# MCU.net
KiCad netlist of a schematic drawn in EAGLE
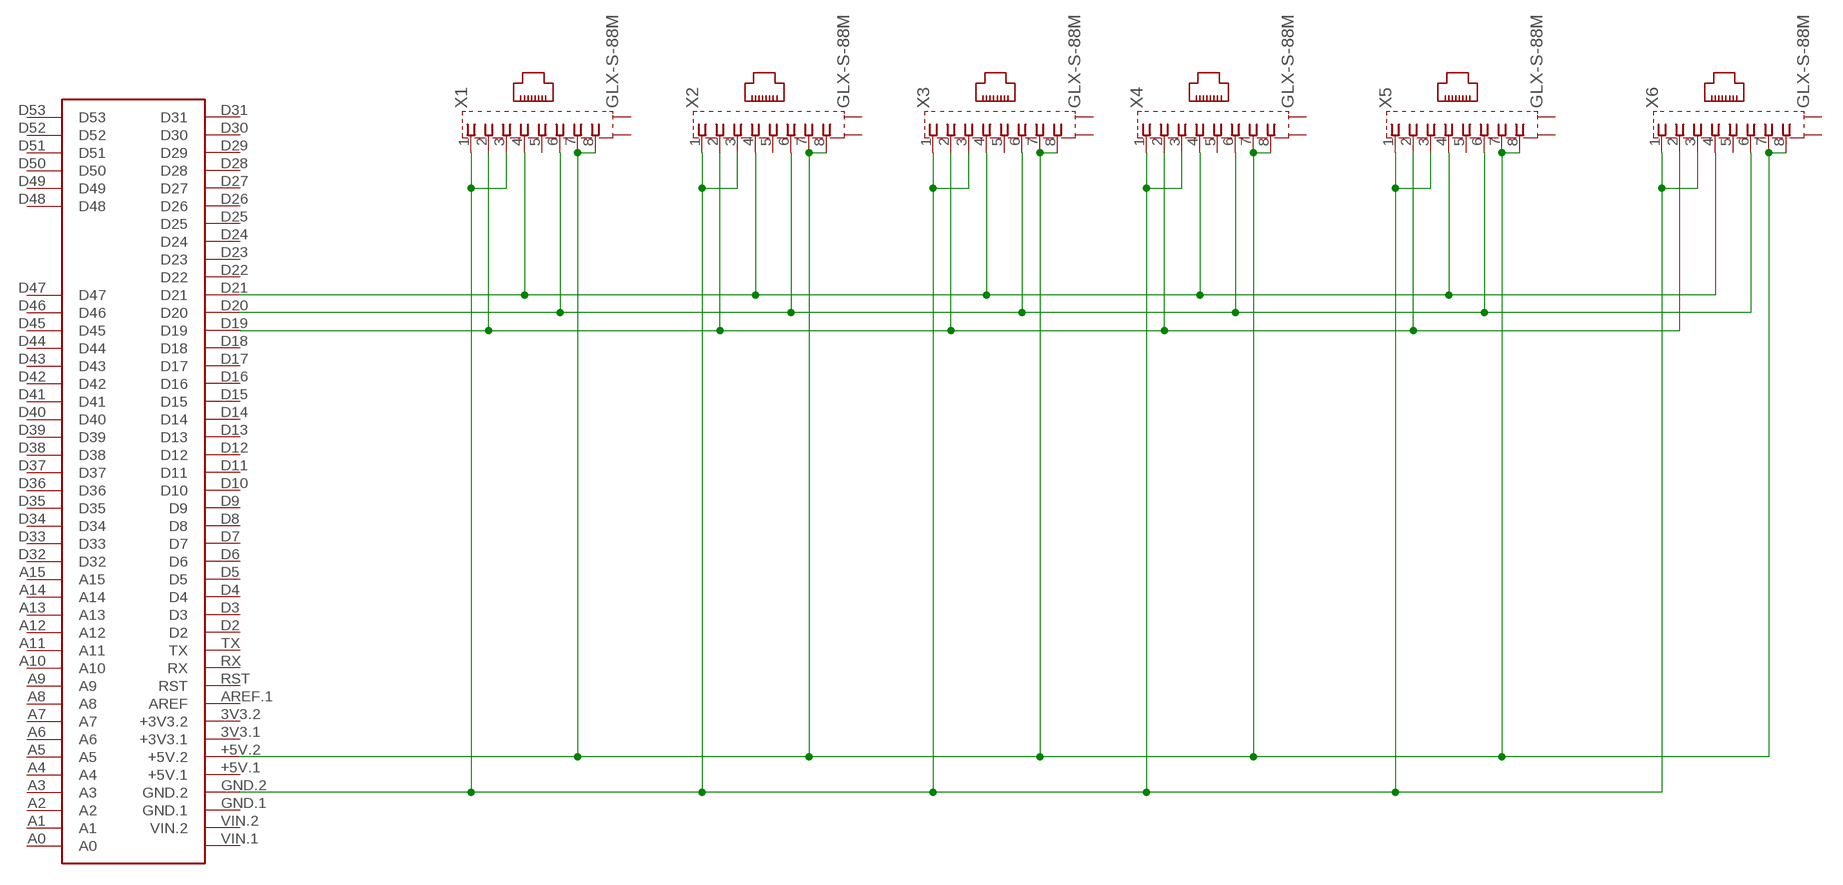
[diagram p0: schematic, sheet 1]

(export (version "E")
  (design (tool "Eeschema 10.0.6"))
  (components
    (comp (ref "U$1")
      (value "MEGA2560_MIKRO")
      (footprint "eagle-import:MEGA2560_MIKRO")
      (libsource (lib "eagle-import") (part "MEGA2560_MIKRO"))
    )
    (comp (ref "X1")
      (value "GLX-S-88M")
      (footprint "eagle-import:GLX-S-88M")
      (libsource (lib "eagle-import") (part "GLX-S-88M"))
    )
    (comp (ref "X2")
      (value "GLX-S-88M")
      (footprint "eagle-import:GLX-S-88M")
      (libsource (lib "eagle-import") (part "GLX-S-88M"))
    )
    (comp (ref "X3")
      (value "GLX-S-88M")
      (footprint "eagle-import:GLX-S-88M")
      (libsource (lib "eagle-import") (part "GLX-S-88M"))
    )
    (comp (ref "X4")
      (value "GLX-S-88M")
      (footprint "eagle-import:GLX-S-88M")
      (libsource (lib "eagle-import") (part "GLX-S-88M"))
    )
    (comp (ref "X5")
      (value "GLX-S-88M")
      (footprint "eagle-import:GLX-S-88M")
      (libsource (lib "eagle-import") (part "GLX-S-88M"))
    )
    (comp (ref "X6")
      (value "GLX-S-88M")
      (footprint "eagle-import:GLX-S-88M")
      (libsource (lib "eagle-import") (part "GLX-S-88M"))
    )
  )
  (nets
    (net (code "1") (name "Net-(U$1-Pad+5V.2)") (class "Default")
      (node (ref "U$1") (pin "+5V.2") (pinfunction "+5V.2_+5V.2") (pintype "bidirectional"))
      (node (ref "X1") (pin "7") (pinfunction "7_7") (pintype "passive"))
      (node (ref "X1") (pin "8") (pinfunction "8_8") (pintype "passive"))
      (node (ref "X2") (pin "7") (pinfunction "7_7") (pintype "passive"))
      (node (ref "X2") (pin "8") (pinfunction "8_8") (pintype "passive"))
      (node (ref "X3") (pin "7") (pinfunction "7_7") (pintype "passive"))
      (node (ref "X3") (pin "8") (pinfunction "8_8") (pintype "passive"))
      (node (ref "X4") (pin "7") (pinfunction "7_7") (pintype "passive"))
      (node (ref "X4") (pin "8") (pinfunction "8_8") (pintype "passive"))
      (node (ref "X5") (pin "7") (pinfunction "7_7") (pintype "passive"))
      (node (ref "X5") (pin "8") (pinfunction "8_8") (pintype "passive"))
      (node (ref "X6") (pin "7") (pinfunction "7_7") (pintype "passive"))
      (node (ref "X6") (pin "8") (pinfunction "8_8") (pintype "passive"))
    )
    (net (code "2") (name "Net-(U$1-PadD19)") (class "Default")
      (node (ref "U$1") (pin "D19") (pinfunction "D19_D19") (pintype "bidirectional"))
      (node (ref "X1") (pin "2") (pinfunction "2_2") (pintype "passive"))
      (node (ref "X2") (pin "2") (pinfunction "2_2") (pintype "passive"))
      (node (ref "X3") (pin "2") (pinfunction "2_2") (pintype "passive"))
      (node (ref "X4") (pin "2") (pinfunction "2_2") (pintype "passive"))
      (node (ref "X5") (pin "2") (pinfunction "2_2") (pintype "passive"))
      (node (ref "X6") (pin "2") (pinfunction "2_2") (pintype "passive"))
    )
    (net (code "3") (name "Net-(U$1-PadD20)") (class "Default")
      (node (ref "U$1") (pin "D20") (pinfunction "D20_D20") (pintype "bidirectional"))
      (node (ref "X1") (pin "6") (pinfunction "6_6") (pintype "passive"))
      (node (ref "X2") (pin "6") (pinfunction "6_6") (pintype "passive"))
      (node (ref "X3") (pin "6") (pinfunction "6_6") (pintype "passive"))
      (node (ref "X4") (pin "6") (pinfunction "6_6") (pintype "passive"))
      (node (ref "X5") (pin "6") (pinfunction "6_6") (pintype "passive"))
      (node (ref "X6") (pin "6") (pinfunction "6_6") (pintype "passive"))
    )
    (net (code "4") (name "Net-(U$1-PadD21)") (class "Default")
      (node (ref "U$1") (pin "D21") (pinfunction "D21_D21") (pintype "bidirectional"))
      (node (ref "X1") (pin "4") (pinfunction "4_4") (pintype "passive"))
      (node (ref "X2") (pin "4") (pinfunction "4_4") (pintype "passive"))
      (node (ref "X3") (pin "4") (pinfunction "4_4") (pintype "passive"))
      (node (ref "X4") (pin "4") (pinfunction "4_4") (pintype "passive"))
      (node (ref "X5") (pin "4") (pinfunction "4_4") (pintype "passive"))
      (node (ref "X6") (pin "4") (pinfunction "4_4") (pintype "passive"))
    )
    (net (code "5") (name "Net-(U$1-PadGND.2)") (class "Default")
      (node (ref "U$1") (pin "GND.2") (pinfunction "GND.2_GND.2") (pintype "bidirectional"))
      (node (ref "X1") (pin "1") (pinfunction "1_1") (pintype "passive"))
      (node (ref "X1") (pin "3") (pinfunction "3_3") (pintype "passive"))
      (node (ref "X2") (pin "1") (pinfunction "1_1") (pintype "passive"))
      (node (ref "X2") (pin "3") (pinfunction "3_3") (pintype "passive"))
      (node (ref "X3") (pin "1") (pinfunction "1_1") (pintype "passive"))
      (node (ref "X3") (pin "3") (pinfunction "3_3") (pintype "passive"))
      (node (ref "X4") (pin "1") (pinfunction "1_1") (pintype "passive"))
      (node (ref "X4") (pin "3") (pinfunction "3_3") (pintype "passive"))
      (node (ref "X5") (pin "1") (pinfunction "1_1") (pintype "passive"))
      (node (ref "X5") (pin "3") (pinfunction "3_3") (pintype "passive"))
      (node (ref "X6") (pin "1") (pinfunction "1_1") (pintype "passive"))
      (node (ref "X6") (pin "3") (pinfunction "3_3") (pintype "passive"))
    )
    (net (code "6") (name "unconnected-(U$1-+3V3.1-Pad3V3.1)") (class "Default")
      (node (ref "U$1") (pin "3V3.1") (pinfunction "+3V3.1_3V3.1") (pintype "bidirectional"))
    )
    (net (code "7") (name "unconnected-(U$1-+3V3.2-Pad3V3.2)") (class "Default")
      (node (ref "U$1") (pin "3V3.2") (pinfunction "+3V3.2_3V3.2") (pintype "bidirectional"))
    )
    (net (code "8") (name "unconnected-(U$1-AREF-PadAREF.1)") (class "Default")
      (node (ref "U$1") (pin "AREF.1") (pinfunction "AREF_AREF.1") (pintype "bidirectional"))
    )
    (net (code "9") (name "unconnected-(U$1-Pad+5V.1)") (class "Default")
      (node (ref "U$1") (pin "+5V.1") (pinfunction "+5V.1_+5V.1") (pintype "bidirectional"))
    )
    (net (code "10") (name "unconnected-(U$1-PadA0)") (class "Default")
      (node (ref "U$1") (pin "A0") (pinfunction "A0_A0") (pintype "bidirectional"))
    )
    (net (code "11") (name "unconnected-(U$1-PadA1)") (class "Default")
      (node (ref "U$1") (pin "A1") (pinfunction "A1_A1") (pintype "bidirectional"))
    )
    (net (code "12") (name "unconnected-(U$1-PadA2)") (class "Default")
      (node (ref "U$1") (pin "A2") (pinfunction "A2_A2") (pintype "bidirectional"))
    )
    (net (code "13") (name "unconnected-(U$1-PadA3)") (class "Default")
      (node (ref "U$1") (pin "A3") (pinfunction "A3_A3") (pintype "bidirectional"))
    )
    (net (code "14") (name "unconnected-(U$1-PadA4)") (class "Default")
      (node (ref "U$1") (pin "A4") (pinfunction "A4_A4") (pintype "bidirectional"))
    )
    (net (code "15") (name "unconnected-(U$1-PadA5)") (class "Default")
      (node (ref "U$1") (pin "A5") (pinfunction "A5_A5") (pintype "bidirectional"))
    )
    (net (code "16") (name "unconnected-(U$1-PadA6)") (class "Default")
      (node (ref "U$1") (pin "A6") (pinfunction "A6_A6") (pintype "bidirectional"))
    )
    (net (code "17") (name "unconnected-(U$1-PadA7)") (class "Default")
      (node (ref "U$1") (pin "A7") (pinfunction "A7_A7") (pintype "bidirectional"))
    )
    (net (code "18") (name "unconnected-(U$1-PadA8)") (class "Default")
      (node (ref "U$1") (pin "A8") (pinfunction "A8_A8") (pintype "bidirectional"))
    )
    (net (code "19") (name "unconnected-(U$1-PadA9)") (class "Default")
      (node (ref "U$1") (pin "A9") (pinfunction "A9_A9") (pintype "bidirectional"))
    )
    (net (code "20") (name "unconnected-(U$1-PadA10)") (class "Default")
      (node (ref "U$1") (pin "A10") (pinfunction "A10_A10") (pintype "bidirectional"))
    )
    (net (code "21") (name "unconnected-(U$1-PadA11)") (class "Default")
      (node (ref "U$1") (pin "A11") (pinfunction "A11_A11") (pintype "bidirectional"))
    )
    (net (code "22") (name "unconnected-(U$1-PadA12)") (class "Default")
      (node (ref "U$1") (pin "A12") (pinfunction "A12_A12") (pintype "bidirectional"))
    )
    (net (code "23") (name "unconnected-(U$1-PadA13)") (class "Default")
      (node (ref "U$1") (pin "A13") (pinfunction "A13_A13") (pintype "bidirectional"))
    )
    (net (code "24") (name "unconnected-(U$1-PadA14)") (class "Default")
      (node (ref "U$1") (pin "A14") (pinfunction "A14_A14") (pintype "bidirectional"))
    )
    (net (code "25") (name "unconnected-(U$1-PadA15)") (class "Default")
      (node (ref "U$1") (pin "A15") (pinfunction "A15_A15") (pintype "bidirectional"))
    )
    (net (code "26") (name "unconnected-(U$1-PadD2)") (class "Default")
      (node (ref "U$1") (pin "D2") (pinfunction "D2_D2") (pintype "bidirectional"))
    )
    (net (code "27") (name "unconnected-(U$1-PadD3)") (class "Default")
      (node (ref "U$1") (pin "D3") (pinfunction "D3_D3") (pintype "bidirectional"))
    )
    (net (code "28") (name "unconnected-(U$1-PadD4)") (class "Default")
      (node (ref "U$1") (pin "D4") (pinfunction "D4_D4") (pintype "bidirectional"))
    )
    (net (code "29") (name "unconnected-(U$1-PadD5)") (class "Default")
      (node (ref "U$1") (pin "D5") (pinfunction "D5_D5") (pintype "bidirectional"))
    )
    (net (code "30") (name "unconnected-(U$1-PadD6)") (class "Default")
      (node (ref "U$1") (pin "D6") (pinfunction "D6_D6") (pintype "bidirectional"))
    )
    (net (code "31") (name "unconnected-(U$1-PadD7)") (class "Default")
      (node (ref "U$1") (pin "D7") (pinfunction "D7_D7") (pintype "bidirectional"))
    )
    (net (code "32") (name "unconnected-(U$1-PadD8)") (class "Default")
      (node (ref "U$1") (pin "D8") (pinfunction "D8_D8") (pintype "bidirectional"))
    )
    (net (code "33") (name "unconnected-(U$1-PadD9)") (class "Default")
      (node (ref "U$1") (pin "D9") (pinfunction "D9_D9") (pintype "bidirectional"))
    )
    (net (code "34") (name "unconnected-(U$1-PadD10)") (class "Default")
      (node (ref "U$1") (pin "D10") (pinfunction "D10_D10") (pintype "bidirectional"))
    )
    (net (code "35") (name "unconnected-(U$1-PadD11)") (class "Default")
      (node (ref "U$1") (pin "D11") (pinfunction "D11_D11") (pintype "bidirectional"))
    )
    (net (code "36") (name "unconnected-(U$1-PadD12)") (class "Default")
      (node (ref "U$1") (pin "D12") (pinfunction "D12_D12") (pintype "bidirectional"))
    )
    (net (code "37") (name "unconnected-(U$1-PadD13)") (class "Default")
      (node (ref "U$1") (pin "D13") (pinfunction "D13_D13") (pintype "bidirectional"))
    )
    (net (code "38") (name "unconnected-(U$1-PadD14)") (class "Default")
      (node (ref "U$1") (pin "D14") (pinfunction "D14_D14") (pintype "bidirectional"))
    )
    (net (code "39") (name "unconnected-(U$1-PadD15)") (class "Default")
      (node (ref "U$1") (pin "D15") (pinfunction "D15_D15") (pintype "bidirectional"))
    )
    (net (code "40") (name "unconnected-(U$1-PadD16)") (class "Default")
      (node (ref "U$1") (pin "D16") (pinfunction "D16_D16") (pintype "bidirectional"))
    )
    (net (code "41") (name "unconnected-(U$1-PadD17)") (class "Default")
      (node (ref "U$1") (pin "D17") (pinfunction "D17_D17") (pintype "bidirectional"))
    )
    (net (code "42") (name "unconnected-(U$1-PadD18)") (class "Default")
      (node (ref "U$1") (pin "D18") (pinfunction "D18_D18") (pintype "bidirectional"))
    )
    (net (code "43") (name "unconnected-(U$1-PadD22)") (class "Default")
      (node (ref "U$1") (pin "D22") (pinfunction "D22_D22") (pintype "bidirectional"))
    )
    (net (code "44") (name "unconnected-(U$1-PadD23)") (class "Default")
      (node (ref "U$1") (pin "D23") (pinfunction "D23_D23") (pintype "bidirectional"))
    )
    (net (code "45") (name "unconnected-(U$1-PadD24)") (class "Default")
      (node (ref "U$1") (pin "D24") (pinfunction "D24_D24") (pintype "bidirectional"))
    )
    (net (code "46") (name "unconnected-(U$1-PadD25)") (class "Default")
      (node (ref "U$1") (pin "D25") (pinfunction "D25_D25") (pintype "bidirectional"))
    )
    (net (code "47") (name "unconnected-(U$1-PadD26)") (class "Default")
      (node (ref "U$1") (pin "D26") (pinfunction "D26_D26") (pintype "bidirectional"))
    )
    (net (code "48") (name "unconnected-(U$1-PadD27)") (class "Default")
      (node (ref "U$1") (pin "D27") (pinfunction "D27_D27") (pintype "bidirectional"))
    )
    (net (code "49") (name "unconnected-(U$1-PadD28)") (class "Default")
      (node (ref "U$1") (pin "D28") (pinfunction "D28_D28") (pintype "bidirectional"))
    )
    (net (code "50") (name "unconnected-(U$1-PadD29)") (class "Default")
      (node (ref "U$1") (pin "D29") (pinfunction "D29_D29") (pintype "bidirectional"))
    )
    (net (code "51") (name "unconnected-(U$1-PadD30)") (class "Default")
      (node (ref "U$1") (pin "D30") (pinfunction "D30_D30") (pintype "bidirectional"))
    )
    (net (code "52") (name "unconnected-(U$1-PadD31)") (class "Default")
      (node (ref "U$1") (pin "D31") (pinfunction "D31_D31") (pintype "bidirectional"))
    )
    (net (code "53") (name "unconnected-(U$1-PadD32)") (class "Default")
      (node (ref "U$1") (pin "D32") (pinfunction "D32_D32") (pintype "bidirectional"))
    )
    (net (code "54") (name "unconnected-(U$1-PadD33)") (class "Default")
      (node (ref "U$1") (pin "D33") (pinfunction "D33_D33") (pintype "bidirectional"))
    )
    (net (code "55") (name "unconnected-(U$1-PadD34)") (class "Default")
      (node (ref "U$1") (pin "D34") (pinfunction "D34_D34") (pintype "bidirectional"))
    )
    (net (code "56") (name "unconnected-(U$1-PadD35)") (class "Default")
      (node (ref "U$1") (pin "D35") (pinfunction "D35_D35") (pintype "bidirectional"))
    )
    (net (code "57") (name "unconnected-(U$1-PadD36)") (class "Default")
      (node (ref "U$1") (pin "D36") (pinfunction "D36_D36") (pintype "bidirectional"))
    )
    (net (code "58") (name "unconnected-(U$1-PadD37)") (class "Default")
      (node (ref "U$1") (pin "D37") (pinfunction "D37_D37") (pintype "bidirectional"))
    )
    (net (code "59") (name "unconnected-(U$1-PadD38)") (class "Default")
      (node (ref "U$1") (pin "D38") (pinfunction "D38_D38") (pintype "bidirectional"))
    )
    (net (code "60") (name "unconnected-(U$1-PadD39)") (class "Default")
      (node (ref "U$1") (pin "D39") (pinfunction "D39_D39") (pintype "bidirectional"))
    )
    (net (code "61") (name "unconnected-(U$1-PadD40)") (class "Default")
      (node (ref "U$1") (pin "D40") (pinfunction "D40_D40") (pintype "bidirectional"))
    )
    (net (code "62") (name "unconnected-(U$1-PadD41)") (class "Default")
      (node (ref "U$1") (pin "D41") (pinfunction "D41_D41") (pintype "bidirectional"))
    )
    (net (code "63") (name "unconnected-(U$1-PadD42)") (class "Default")
      (node (ref "U$1") (pin "D42") (pinfunction "D42_D42") (pintype "bidirectional"))
    )
    (net (code "64") (name "unconnected-(U$1-PadD43)") (class "Default")
      (node (ref "U$1") (pin "D43") (pinfunction "D43_D43") (pintype "bidirectional"))
    )
    (net (code "65") (name "unconnected-(U$1-PadD44)") (class "Default")
      (node (ref "U$1") (pin "D44") (pinfunction "D44_D44") (pintype "bidirectional"))
    )
    (net (code "66") (name "unconnected-(U$1-PadD45)") (class "Default")
      (node (ref "U$1") (pin "D45") (pinfunction "D45_D45") (pintype "bidirectional"))
    )
    (net (code "67") (name "unconnected-(U$1-PadD46)") (class "Default")
      (node (ref "U$1") (pin "D46") (pinfunction "D46_D46") (pintype "bidirectional"))
    )
    (net (code "68") (name "unconnected-(U$1-PadD47)") (class "Default")
      (node (ref "U$1") (pin "D47") (pinfunction "D47_D47") (pintype "bidirectional"))
    )
    (net (code "69") (name "unconnected-(U$1-PadD48)") (class "Default")
      (node (ref "U$1") (pin "D48") (pinfunction "D48_D48") (pintype "bidirectional"))
    )
    (net (code "70") (name "unconnected-(U$1-PadD49)") (class "Default")
      (node (ref "U$1") (pin "D49") (pinfunction "D49_D49") (pintype "bidirectional"))
    )
    (net (code "71") (name "unconnected-(U$1-PadD50)") (class "Default")
      (node (ref "U$1") (pin "D50") (pinfunction "D50_D50") (pintype "bidirectional"))
    )
    (net (code "72") (name "unconnected-(U$1-PadD51)") (class "Default")
      (node (ref "U$1") (pin "D51") (pinfunction "D51_D51") (pintype "bidirectional"))
    )
    (net (code "73") (name "unconnected-(U$1-PadD52)") (class "Default")
      (node (ref "U$1") (pin "D52") (pinfunction "D52_D52") (pintype "bidirectional"))
    )
    (net (code "74") (name "unconnected-(U$1-PadD53)") (class "Default")
      (node (ref "U$1") (pin "D53") (pinfunction "D53_D53") (pintype "bidirectional"))
    )
    (net (code "75") (name "unconnected-(U$1-PadGND.1)") (class "Default")
      (node (ref "U$1") (pin "GND.1") (pinfunction "GND.1_GND.1") (pintype "bidirectional"))
    )
    (net (code "76") (name "unconnected-(U$1-PadRST)") (class "Default")
      (node (ref "U$1") (pin "RST") (pinfunction "RST_RST") (pintype "bidirectional"))
    )
    (net (code "77") (name "unconnected-(U$1-PadRX)") (class "Default")
      (node (ref "U$1") (pin "RX") (pinfunction "RX_RX") (pintype "bidirectional"))
    )
    (net (code "78") (name "unconnected-(U$1-PadTX)") (class "Default")
      (node (ref "U$1") (pin "TX") (pinfunction "TX_TX") (pintype "bidirectional"))
    )
    (net (code "79") (name "unconnected-(U$1-PadVIN.1)") (class "Default")
      (node (ref "U$1") (pin "VIN.1") (pinfunction "VIN.1_VIN.1") (pintype "bidirectional"))
    )
    (net (code "80") (name "unconnected-(U$1-PadVIN.2)") (class "Default")
      (node (ref "U$1") (pin "VIN.2") (pinfunction "VIN.2_VIN.2") (pintype "bidirectional"))
    )
    (net (code "81") (name "unconnected-(X1-Pad5)") (class "Default")
      (node (ref "X1") (pin "5") (pinfunction "5_5") (pintype "passive"))
    )
    (net (code "82") (name "unconnected-(X1-PadS1)") (class "Default")
      (node (ref "X1") (pin "S1") (pinfunction "S1_S1") (pintype "passive"))
    )
    (net (code "83") (name "unconnected-(X1-PadS2)") (class "Default")
      (node (ref "X1") (pin "S2") (pinfunction "S2_S2") (pintype "passive"))
    )
    (net (code "84") (name "unconnected-(X2-Pad5)") (class "Default")
      (node (ref "X2") (pin "5") (pinfunction "5_5") (pintype "passive"))
    )
    (net (code "85") (name "unconnected-(X2-PadS1)") (class "Default")
      (node (ref "X2") (pin "S1") (pinfunction "S1_S1") (pintype "passive"))
    )
    (net (code "86") (name "unconnected-(X2-PadS2)") (class "Default")
      (node (ref "X2") (pin "S2") (pinfunction "S2_S2") (pintype "passive"))
    )
    (net (code "87") (name "unconnected-(X3-Pad5)") (class "Default")
      (node (ref "X3") (pin "5") (pinfunction "5_5") (pintype "passive"))
    )
    (net (code "88") (name "unconnected-(X3-PadS1)") (class "Default")
      (node (ref "X3") (pin "S1") (pinfunction "S1_S1") (pintype "passive"))
    )
    (net (code "89") (name "unconnected-(X3-PadS2)") (class "Default")
      (node (ref "X3") (pin "S2") (pinfunction "S2_S2") (pintype "passive"))
    )
    (net (code "90") (name "unconnected-(X4-Pad5)") (class "Default")
      (node (ref "X4") (pin "5") (pinfunction "5_5") (pintype "passive"))
    )
    (net (code "91") (name "unconnected-(X4-PadS1)") (class "Default")
      (node (ref "X4") (pin "S1") (pinfunction "S1_S1") (pintype "passive"))
    )
    (net (code "92") (name "unconnected-(X4-PadS2)") (class "Default")
      (node (ref "X4") (pin "S2") (pinfunction "S2_S2") (pintype "passive"))
    )
    (net (code "93") (name "unconnected-(X5-Pad5)") (class "Default")
      (node (ref "X5") (pin "5") (pinfunction "5_5") (pintype "passive"))
    )
    (net (code "94") (name "unconnected-(X5-PadS1)") (class "Default")
      (node (ref "X5") (pin "S1") (pinfunction "S1_S1") (pintype "passive"))
    )
    (net (code "95") (name "unconnected-(X5-PadS2)") (class "Default")
      (node (ref "X5") (pin "S2") (pinfunction "S2_S2") (pintype "passive"))
    )
    (net (code "96") (name "unconnected-(X6-Pad5)") (class "Default")
      (node (ref "X6") (pin "5") (pinfunction "5_5") (pintype "passive"))
    )
    (net (code "97") (name "unconnected-(X6-PadS1)") (class "Default")
      (node (ref "X6") (pin "S1") (pinfunction "S1_S1") (pintype "passive"))
    )
    (net (code "98") (name "unconnected-(X6-PadS2)") (class "Default")
      (node (ref "X6") (pin "S2") (pinfunction "S2_S2") (pintype "passive"))
    )
  )
)
